# gpio.net
KiCad netlist of a schematic drawn in Altium Designer
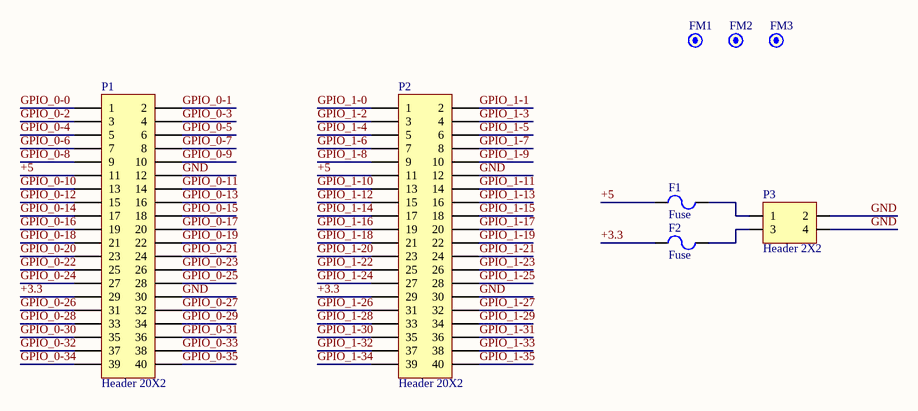
[diagram p0: gpio.SchDoc]

(export (version "E")
  (design (tool "Eeschema 10.0.6"))
  (components
    (comp (ref "F1") (value "Fuse") (footprint "Fuse 1206") (libsource (lib "chipfc_libs") (part "Fuse")))
    (comp (ref "F2") (value "Fuse") (footprint "Fuse 1206") (libsource (lib "chipfc_libs") (part "Fuse")))
    (comp (ref "FM1")
      (value "Fiducial")
      (footprint "Fiducial")
      (description "Fiducial Marker")
      (libsource (lib "bnhh") (part "Fiducial"))
    )
    (comp (ref "FM2")
      (value "Fiducial")
      (footprint "Fiducial")
      (description "Fiducial Marker")
      (libsource (lib "bnhh") (part "Fiducial"))
    )
    (comp (ref "FM3")
      (value "Fiducial")
      (footprint "Fiducial")
      (description "Fiducial Marker")
      (libsource (lib "bnhh") (part "Fiducial"))
    )
    (comp (ref "P1")
      (value "Header 20X2")
      (footprint "Header FM 2x20")
      (description "Header, 20-Pin, Dual row")
      (fields (field (name "PUBLISHER") "Altium Limited"))
      (libsource (lib "My library altium") (part "Header 20X2"))
    )
    (comp (ref "P2")
      (value "Header 20X2")
      (footprint "Header FM 2x20")
      (description "Header, 20-Pin, Dual row")
      (fields (field (name "PUBLISHER") "Altium Limited"))
      (libsource (lib "My library altium") (part "Header 20X2"))
    )
    (comp (ref "P3")
      (value "Header 2X2")
      (footprint "HDR/Header/4/DL")
      (description "Header, 2-Pin, Dual row")
      (libsource (lib "connectors") (part "Header 2X2"))
    )
  )
  (nets
    (net (code "1") (name "/+3.3") (class "Default")
      (node (ref "F2") (pin "1") (pinfunction "1_1") (pintype "passive"))
      (node (ref "P1") (pin "29") (pinfunction "29_29") (pintype "passive"))
      (node (ref "P2") (pin "29") (pinfunction "29_29") (pintype "passive"))
    )
    (net (code "2") (name "/+5") (class "Default")
      (node (ref "F1") (pin "1") (pinfunction "1_1") (pintype "passive"))
      (node (ref "P1") (pin "11") (pinfunction "11_11") (pintype "passive"))
      (node (ref "P2") (pin "11") (pinfunction "11_11") (pintype "passive"))
    )
    (net (code "3") (name "/GND") (class "Default")
      (node (ref "P1") (pin "12") (pinfunction "12_12") (pintype "passive"))
      (node (ref "P1") (pin "30") (pinfunction "30_30") (pintype "passive"))
      (node (ref "P2") (pin "12") (pinfunction "12_12") (pintype "passive"))
      (node (ref "P2") (pin "30") (pinfunction "30_30") (pintype "passive"))
      (node (ref "P3") (pin "2") (pinfunction "2_2") (pintype "passive"))
      (node (ref "P3") (pin "4") (pinfunction "4_4") (pintype "passive"))
    )
    (net (code "4") (name "/GPIO_0-0") (class "Default")
      (node (ref "P1") (pin "1") (pinfunction "1_1") (pintype "passive"))
    )
    (net (code "5") (name "/GPIO_0-1") (class "Default")
      (node (ref "P1") (pin "2") (pinfunction "2_2") (pintype "passive"))
    )
    (net (code "6") (name "/GPIO_0-2") (class "Default")
      (node (ref "P1") (pin "3") (pinfunction "3_3") (pintype "passive"))
    )
    (net (code "7") (name "/GPIO_0-3") (class "Default")
      (node (ref "P1") (pin "4") (pinfunction "4_4") (pintype "passive"))
    )
    (net (code "8") (name "/GPIO_0-4") (class "Default")
      (node (ref "P1") (pin "5") (pinfunction "5_5") (pintype "passive"))
    )
    (net (code "9") (name "/GPIO_0-5") (class "Default")
      (node (ref "P1") (pin "6") (pinfunction "6_6") (pintype "passive"))
    )
    (net (code "10") (name "/GPIO_0-6") (class "Default")
      (node (ref "P1") (pin "7") (pinfunction "7_7") (pintype "passive"))
    )
    (net (code "11") (name "/GPIO_0-7") (class "Default")
      (node (ref "P1") (pin "8") (pinfunction "8_8") (pintype "passive"))
    )
    (net (code "12") (name "/GPIO_0-8") (class "Default")
      (node (ref "P1") (pin "9") (pinfunction "9_9") (pintype "passive"))
    )
    (net (code "13") (name "/GPIO_0-9") (class "Default")
      (node (ref "P1") (pin "10") (pinfunction "10_10") (pintype "passive"))
    )
    (net (code "14") (name "/GPIO_0-10") (class "Default")
      (node (ref "P1") (pin "13") (pinfunction "13_13") (pintype "passive"))
    )
    (net (code "15") (name "/GPIO_0-11") (class "Default")
      (node (ref "P1") (pin "14") (pinfunction "14_14") (pintype "passive"))
    )
    (net (code "16") (name "/GPIO_0-12") (class "Default")
      (node (ref "P1") (pin "15") (pinfunction "15_15") (pintype "passive"))
    )
    (net (code "17") (name "/GPIO_0-13") (class "Default")
      (node (ref "P1") (pin "16") (pinfunction "16_16") (pintype "passive"))
    )
    (net (code "18") (name "/GPIO_0-14") (class "Default")
      (node (ref "P1") (pin "17") (pinfunction "17_17") (pintype "passive"))
    )
    (net (code "19") (name "/GPIO_0-15") (class "Default")
      (node (ref "P1") (pin "18") (pinfunction "18_18") (pintype "passive"))
    )
    (net (code "20") (name "/GPIO_0-16") (class "Default")
      (node (ref "P1") (pin "19") (pinfunction "19_19") (pintype "passive"))
    )
    (net (code "21") (name "/GPIO_0-17") (class "Default")
      (node (ref "P1") (pin "20") (pinfunction "20_20") (pintype "passive"))
    )
    (net (code "22") (name "/GPIO_0-18") (class "Default")
      (node (ref "P1") (pin "21") (pinfunction "21_21") (pintype "passive"))
    )
    (net (code "23") (name "/GPIO_0-19") (class "Default")
      (node (ref "P1") (pin "22") (pinfunction "22_22") (pintype "passive"))
    )
    (net (code "24") (name "/GPIO_0-20") (class "Default")
      (node (ref "P1") (pin "23") (pinfunction "23_23") (pintype "passive"))
    )
    (net (code "25") (name "/GPIO_0-21") (class "Default")
      (node (ref "P1") (pin "24") (pinfunction "24_24") (pintype "passive"))
    )
    (net (code "26") (name "/GPIO_0-22") (class "Default")
      (node (ref "P1") (pin "25") (pinfunction "25_25") (pintype "passive"))
    )
    (net (code "27") (name "/GPIO_0-23") (class "Default")
      (node (ref "P1") (pin "26") (pinfunction "26_26") (pintype "passive"))
    )
    (net (code "28") (name "/GPIO_0-24") (class "Default")
      (node (ref "P1") (pin "27") (pinfunction "27_27") (pintype "passive"))
    )
    (net (code "29") (name "/GPIO_0-25") (class "Default")
      (node (ref "P1") (pin "28") (pinfunction "28_28") (pintype "passive"))
    )
    (net (code "30") (name "/GPIO_0-26") (class "Default")
      (node (ref "P1") (pin "31") (pinfunction "31_31") (pintype "passive"))
    )
    (net (code "31") (name "/GPIO_0-27") (class "Default")
      (node (ref "P1") (pin "32") (pinfunction "32_32") (pintype "passive"))
    )
    (net (code "32") (name "/GPIO_0-28") (class "Default")
      (node (ref "P1") (pin "33") (pinfunction "33_33") (pintype "passive"))
    )
    (net (code "33") (name "/GPIO_0-29") (class "Default")
      (node (ref "P1") (pin "34") (pinfunction "34_34") (pintype "passive"))
    )
    (net (code "34") (name "/GPIO_0-30") (class "Default")
      (node (ref "P1") (pin "35") (pinfunction "35_35") (pintype "passive"))
    )
    (net (code "35") (name "/GPIO_0-31") (class "Default")
      (node (ref "P1") (pin "36") (pinfunction "36_36") (pintype "passive"))
    )
    (net (code "36") (name "/GPIO_0-32") (class "Default")
      (node (ref "P1") (pin "37") (pinfunction "37_37") (pintype "passive"))
    )
    (net (code "37") (name "/GPIO_0-33") (class "Default")
      (node (ref "P1") (pin "38") (pinfunction "38_38") (pintype "passive"))
    )
    (net (code "38") (name "/GPIO_0-34") (class "Default")
      (node (ref "P1") (pin "39") (pinfunction "39_39") (pintype "passive"))
    )
    (net (code "39") (name "/GPIO_0-35") (class "Default")
      (node (ref "P1") (pin "40") (pinfunction "40_40") (pintype "passive"))
    )
    (net (code "40") (name "/GPIO_1-0") (class "Default")
      (node (ref "P2") (pin "1") (pinfunction "1_1") (pintype "passive"))
    )
    (net (code "41") (name "/GPIO_1-1") (class "Default")
      (node (ref "P2") (pin "2") (pinfunction "2_2") (pintype "passive"))
    )
    (net (code "42") (name "/GPIO_1-2") (class "Default")
      (node (ref "P2") (pin "3") (pinfunction "3_3") (pintype "passive"))
    )
    (net (code "43") (name "/GPIO_1-3") (class "Default")
      (node (ref "P2") (pin "4") (pinfunction "4_4") (pintype "passive"))
    )
    (net (code "44") (name "/GPIO_1-4") (class "Default")
      (node (ref "P2") (pin "5") (pinfunction "5_5") (pintype "passive"))
    )
    (net (code "45") (name "/GPIO_1-5") (class "Default")
      (node (ref "P2") (pin "6") (pinfunction "6_6") (pintype "passive"))
    )
    (net (code "46") (name "/GPIO_1-6") (class "Default")
      (node (ref "P2") (pin "7") (pinfunction "7_7") (pintype "passive"))
    )
    (net (code "47") (name "/GPIO_1-7") (class "Default")
      (node (ref "P2") (pin "8") (pinfunction "8_8") (pintype "passive"))
    )
    (net (code "48") (name "/GPIO_1-8") (class "Default")
      (node (ref "P2") (pin "9") (pinfunction "9_9") (pintype "passive"))
    )
    (net (code "49") (name "/GPIO_1-9") (class "Default")
      (node (ref "P2") (pin "10") (pinfunction "10_10") (pintype "passive"))
    )
    (net (code "50") (name "/GPIO_1-10") (class "Default")
      (node (ref "P2") (pin "13") (pinfunction "13_13") (pintype "passive"))
    )
    (net (code "51") (name "/GPIO_1-11") (class "Default")
      (node (ref "P2") (pin "14") (pinfunction "14_14") (pintype "passive"))
    )
    (net (code "52") (name "/GPIO_1-12") (class "Default")
      (node (ref "P2") (pin "15") (pinfunction "15_15") (pintype "passive"))
    )
    (net (code "53") (name "/GPIO_1-13") (class "Default")
      (node (ref "P2") (pin "16") (pinfunction "16_16") (pintype "passive"))
    )
    (net (code "54") (name "/GPIO_1-14") (class "Default")
      (node (ref "P2") (pin "17") (pinfunction "17_17") (pintype "passive"))
    )
    (net (code "55") (name "/GPIO_1-15") (class "Default")
      (node (ref "P2") (pin "18") (pinfunction "18_18") (pintype "passive"))
    )
    (net (code "56") (name "/GPIO_1-16") (class "Default")
      (node (ref "P2") (pin "19") (pinfunction "19_19") (pintype "passive"))
    )
    (net (code "57") (name "/GPIO_1-17") (class "Default")
      (node (ref "P2") (pin "20") (pinfunction "20_20") (pintype "passive"))
    )
    (net (code "58") (name "/GPIO_1-18") (class "Default")
      (node (ref "P2") (pin "21") (pinfunction "21_21") (pintype "passive"))
    )
    (net (code "59") (name "/GPIO_1-19") (class "Default")
      (node (ref "P2") (pin "22") (pinfunction "22_22") (pintype "passive"))
    )
    (net (code "60") (name "/GPIO_1-20") (class "Default")
      (node (ref "P2") (pin "23") (pinfunction "23_23") (pintype "passive"))
    )
    (net (code "61") (name "/GPIO_1-21") (class "Default")
      (node (ref "P2") (pin "24") (pinfunction "24_24") (pintype "passive"))
    )
    (net (code "62") (name "/GPIO_1-22") (class "Default")
      (node (ref "P2") (pin "25") (pinfunction "25_25") (pintype "passive"))
    )
    (net (code "63") (name "/GPIO_1-23") (class "Default")
      (node (ref "P2") (pin "26") (pinfunction "26_26") (pintype "passive"))
    )
    (net (code "64") (name "/GPIO_1-24") (class "Default")
      (node (ref "P2") (pin "27") (pinfunction "27_27") (pintype "passive"))
    )
    (net (code "65") (name "/GPIO_1-25") (class "Default")
      (node (ref "P2") (pin "28") (pinfunction "28_28") (pintype "passive"))
    )
    (net (code "66") (name "/GPIO_1-26") (class "Default")
      (node (ref "P2") (pin "31") (pinfunction "31_31") (pintype "passive"))
    )
    (net (code "67") (name "/GPIO_1-27") (class "Default")
      (node (ref "P2") (pin "32") (pinfunction "32_32") (pintype "passive"))
    )
    (net (code "68") (name "/GPIO_1-28") (class "Default")
      (node (ref "P2") (pin "33") (pinfunction "33_33") (pintype "passive"))
    )
    (net (code "69") (name "/GPIO_1-29") (class "Default")
      (node (ref "P2") (pin "34") (pinfunction "34_34") (pintype "passive"))
    )
    (net (code "70") (name "/GPIO_1-30") (class "Default")
      (node (ref "P2") (pin "35") (pinfunction "35_35") (pintype "passive"))
    )
    (net (code "71") (name "/GPIO_1-31") (class "Default")
      (node (ref "P2") (pin "36") (pinfunction "36_36") (pintype "passive"))
    )
    (net (code "72") (name "/GPIO_1-32") (class "Default")
      (node (ref "P2") (pin "37") (pinfunction "37_37") (pintype "passive"))
    )
    (net (code "73") (name "/GPIO_1-33") (class "Default")
      (node (ref "P2") (pin "38") (pinfunction "38_38") (pintype "passive"))
    )
    (net (code "74") (name "/GPIO_1-34") (class "Default")
      (node (ref "P2") (pin "39") (pinfunction "39_39") (pintype "passive"))
    )
    (net (code "75") (name "/GPIO_1-35") (class "Default")
      (node (ref "P2") (pin "40") (pinfunction "40_40") (pintype "passive"))
    )
    (net (code "76") (name "Net-(F1-Pad2)") (class "Default")
      (node (ref "F1") (pin "2") (pinfunction "2_2") (pintype "passive"))
      (node (ref "P3") (pin "1") (pinfunction "1_1") (pintype "passive"))
    )
    (net (code "77") (name "Net-(F2-Pad2)") (class "Default")
      (node (ref "F2") (pin "2") (pinfunction "2_2") (pintype "passive"))
      (node (ref "P3") (pin "3") (pinfunction "3_3") (pintype "passive"))
    )
  )
)
